# power.net
KiCad netlist of a schematic drawn in EAGLE
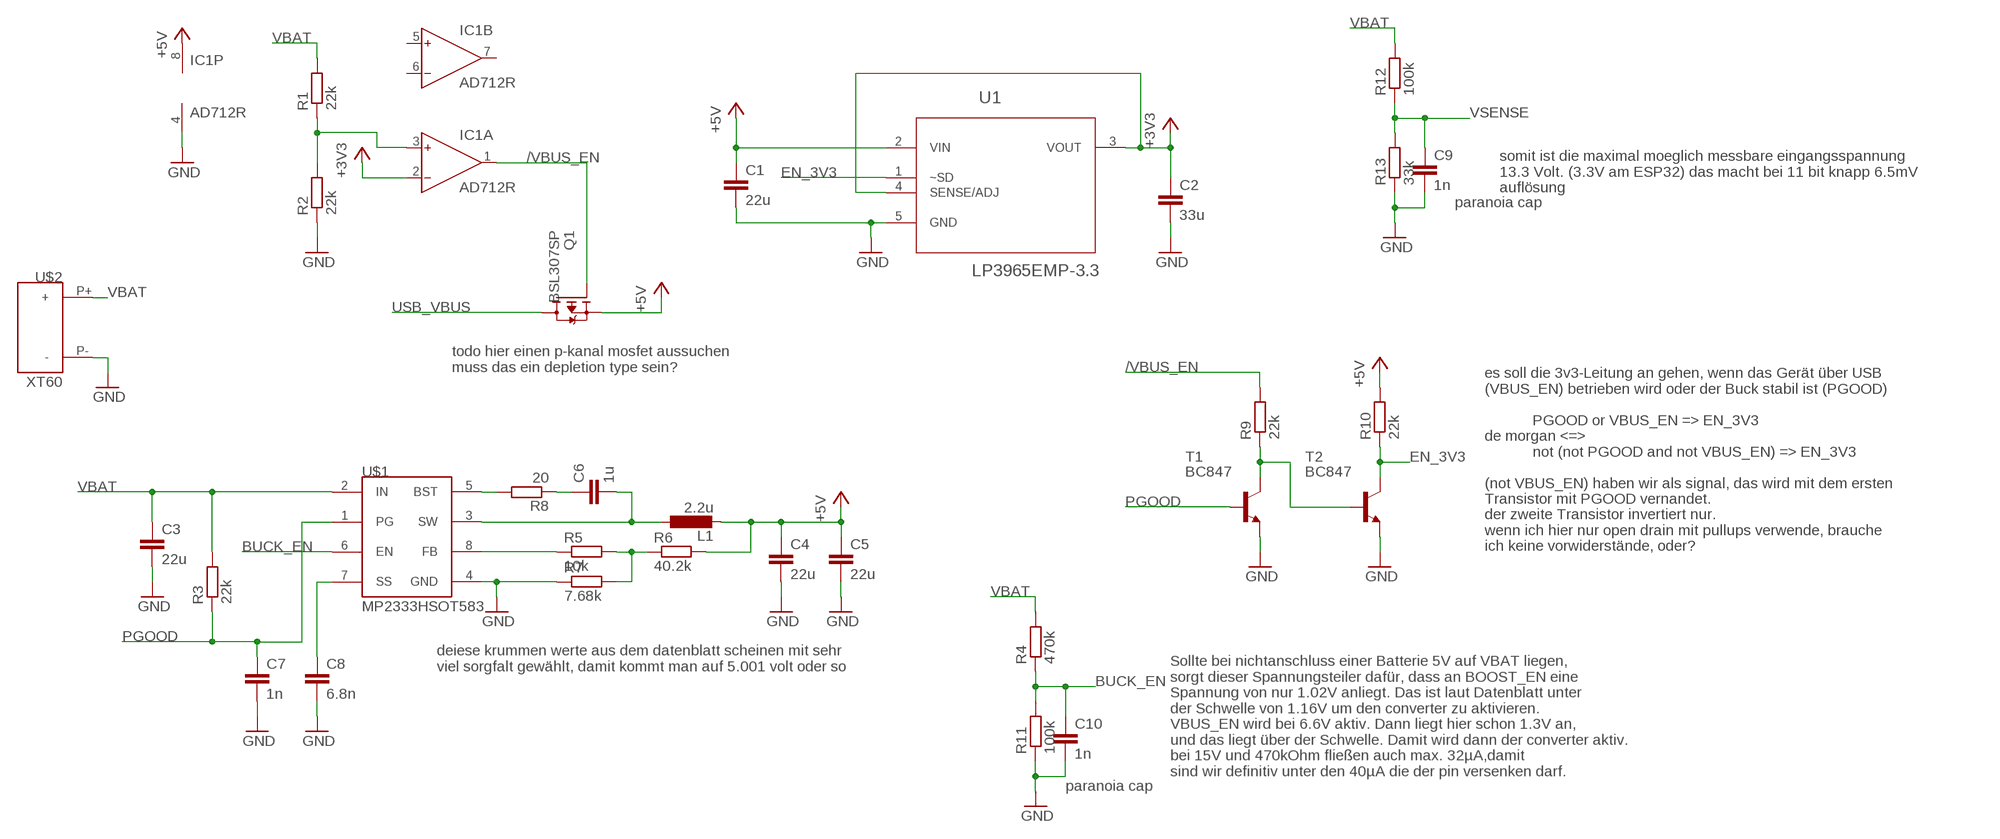
[diagram p0: schematic, sheet 1]

(export (version "E")
  (design (tool "Eeschema 10.0.6"))
  (components
    (comp (ref "C1")
      (value "22u")
      (footprint "eagle-import:C0603")
      (libsource (lib "eagle-import") (part "C-EUC0603"))
    )
    (comp (ref "C2")
      (value "33u")
      (footprint "eagle-import:C0603")
      (libsource (lib "eagle-import") (part "C-EUC0603"))
    )
    (comp (ref "C3")
      (value "22u")
      (footprint "eagle-import:C0805")
      (libsource (lib "eagle-import") (part "C-EUC0805"))
    )
    (comp (ref "C4")
      (value "22u")
      (footprint "eagle-import:C0805")
      (libsource (lib "eagle-import") (part "C-EUC0805"))
    )
    (comp (ref "C5")
      (value "22u")
      (footprint "eagle-import:C0805")
      (libsource (lib "eagle-import") (part "C-EUC0805"))
    )
    (comp (ref "C6")
      (value "1u")
      (footprint "eagle-import:C0805")
      (libsource (lib "eagle-import") (part "C-EUC0805"))
    )
    (comp (ref "C7")
      (value "1n")
      (footprint "eagle-import:C0603")
      (libsource (lib "eagle-import") (part "C-EUC0603"))
    )
    (comp (ref "C8")
      (value "6.8n")
      (footprint "eagle-import:C0603")
      (libsource (lib "eagle-import") (part "C-EUC0603"))
    )
    (comp (ref "C9")
      (value "1n")
      (footprint "eagle-import:C0603")
      (libsource (lib "eagle-import") (part "C-EUC0603"))
    )
    (comp (ref "C10")
      (value "1n")
      (footprint "eagle-import:C0603")
      (libsource (lib "eagle-import") (part "C-EUC0603"))
    )
    (comp (ref "IC1")
      (value "AD712R")
      (footprint "eagle-import:SO8")
      (fields (field (name "MF") "ALTERA CORPORATION") (field (name "MPN") "AD712KRZ"))
      (libsource (lib "eagle-import") (part "AD712R"))
    )
    (comp (ref "L1")
      (value "2.2u")
      (footprint "eagle-import:PIS2816")
      (libsource (lib "eagle-import") (part "L-EUPIS2816"))
    )
    (comp (ref "Q1")
      (value "BSL307SP")
      (footprint "eagle-import:SC74_INFINEON")
      (libsource (lib "eagle-import") (part "BSL307SP"))
    )
    (comp (ref "R1")
      (value "22k")
      (footprint "eagle-import:R0603")
      (libsource (lib "eagle-import") (part "R-EU_R0603"))
    )
    (comp (ref "R2")
      (value "22k")
      (footprint "eagle-import:R0603")
      (libsource (lib "eagle-import") (part "R-EU_R0603"))
    )
    (comp (ref "R3")
      (value "22k")
      (footprint "eagle-import:R0603")
      (libsource (lib "eagle-import") (part "R-EU_R0603"))
    )
    (comp (ref "R4")
      (value "470k")
      (footprint "eagle-import:R0603")
      (libsource (lib "eagle-import") (part "R-EU_R0603"))
    )
    (comp (ref "R5")
      (value "10k")
      (footprint "eagle-import:R0603")
      (libsource (lib "eagle-import") (part "R-EU_R0603"))
    )
    (comp (ref "R6")
      (value "40.2k")
      (footprint "eagle-import:R0603")
      (libsource (lib "eagle-import") (part "R-EU_R0603"))
    )
    (comp (ref "R7")
      (value "7.68k")
      (footprint "eagle-import:R0603")
      (libsource (lib "eagle-import") (part "R-EU_R0603"))
    )
    (comp (ref "R8")
      (value "20")
      (footprint "eagle-import:R0603")
      (libsource (lib "eagle-import") (part "R-EU_R0603"))
    )
    (comp (ref "R9")
      (value "22k")
      (footprint "eagle-import:R0603")
      (libsource (lib "eagle-import") (part "R-EU_R0603"))
    )
    (comp (ref "R10")
      (value "22k")
      (footprint "eagle-import:R0603")
      (libsource (lib "eagle-import") (part "R-EU_R0603"))
    )
    (comp (ref "R11")
      (value "100k")
      (footprint "eagle-import:R0603")
      (libsource (lib "eagle-import") (part "R-EU_R0603"))
    )
    (comp (ref "R12")
      (value "100k")
      (footprint "eagle-import:R0603")
      (libsource (lib "eagle-import") (part "R-EU_R0603"))
    )
    (comp (ref "R13")
      (value "33k")
      (footprint "eagle-import:R0603")
      (libsource (lib "eagle-import") (part "R-EU_R0603"))
    )
    (comp (ref "T1")
      (value "BC847")
      (footprint "eagle-import:SOT23")
      (libsource (lib "eagle-import") (part "BC847"))
    )
    (comp (ref "T2")
      (value "BC847")
      (footprint "eagle-import:SOT23")
      (libsource (lib "eagle-import") (part "BC847"))
    )
    (comp (ref "U$1")
      (value "MP2333HSOT583")
      (footprint "eagle-import:SOTFL50P175X60-8N")
      (libsource (lib "eagle-import") (part "MP2333HSOT583"))
    )
    (comp (ref "U$2")
      (value "XT60")
      (footprint "eagle-import:XT60-UPRIGHT")
      (libsource (lib "eagle-import") (part "XT60"))
    )
    (comp (ref "U1")
      (value "LP3965EMP-3.3")
      (footprint "eagle-import:SOT150P696X180-5N")
      (fields (field (name "MF") "Texas Instruments") (field (name "MP") "LP3965EMP-3.3/NOPB"))
      (libsource (lib "eagle-import") (part "LP3965EMP-3.3"))
    )
  )
  (nets
    (net (code "1") (name "+3V3") (class "Default")
      (node (ref "C2") (pin "1") (pinfunction "1_1") (pintype "passive"))
      (node (ref "IC1") (pin "2") (pinfunction "IN-_2") (pintype "input"))
      (node (ref "U1") (pin "3") (pinfunction "VOUT_3") (pintype "passive"))
      (node (ref "U1") (pin "4") (pinfunction "SENSE/ADJ_4") (pintype "input"))
    )
    (net (code "2") (name "+5V") (class "Default")
      (node (ref "C1") (pin "1") (pinfunction "1_1") (pintype "passive"))
      (node (ref "C4") (pin "1") (pinfunction "1_1") (pintype "passive"))
      (node (ref "C5") (pin "1") (pinfunction "1_1") (pintype "passive"))
      (node (ref "IC1") (pin "8") (pinfunction "V+_8") (pintype "power_in"))
      (node (ref "L1") (pin "2") (pinfunction "2_2") (pintype "passive"))
      (node (ref "Q1") (pin "4") (pinfunction "S_4") (pintype "passive"))
      (node (ref "R10") (pin "2") (pinfunction "2_2") (pintype "passive"))
      (node (ref "R6") (pin "2") (pinfunction "2_2") (pintype "passive"))
      (node (ref "U1") (pin "2") (pinfunction "VIN_2") (pintype "input"))
    )
    (net (code "3") (name "BUCK_EN") (class "Default")
      (node (ref "C10") (pin "1") (pinfunction "1_1") (pintype "passive"))
      (node (ref "R11") (pin "2") (pinfunction "2_2") (pintype "passive"))
      (node (ref "R4") (pin "1") (pinfunction "1_1") (pintype "passive"))
      (node (ref "U$1") (pin "6") (pinfunction "EN_6") (pintype "input"))
    )
    (net (code "4") (name "EN_3V3") (class "Default")
      (node (ref "R10") (pin "1") (pinfunction "1_1") (pintype "passive"))
      (node (ref "T2") (pin "3") (pinfunction "C_3") (pintype "passive"))
      (node (ref "U1") (pin "1") (pinfunction "~{SD}_1") (pintype "input"))
    )
    (net (code "5") (name "GND") (class "Default")
      (node (ref "C1") (pin "2") (pinfunction "2_2") (pintype "passive"))
      (node (ref "C10") (pin "2") (pinfunction "2_2") (pintype "passive"))
      (node (ref "C2") (pin "2") (pinfunction "2_2") (pintype "passive"))
      (node (ref "C3") (pin "2") (pinfunction "2_2") (pintype "passive"))
      (node (ref "C4") (pin "2") (pinfunction "2_2") (pintype "passive"))
      (node (ref "C5") (pin "2") (pinfunction "2_2") (pintype "passive"))
      (node (ref "C7") (pin "2") (pinfunction "2_2") (pintype "passive"))
      (node (ref "C8") (pin "2") (pinfunction "2_2") (pintype "passive"))
      (node (ref "C9") (pin "2") (pinfunction "2_2") (pintype "passive"))
      (node (ref "IC1") (pin "4") (pinfunction "V-_4") (pintype "power_in"))
      (node (ref "R11") (pin "1") (pinfunction "1_1") (pintype "passive"))
      (node (ref "R13") (pin "1") (pinfunction "1_1") (pintype "passive"))
      (node (ref "R2") (pin "1") (pinfunction "1_1") (pintype "passive"))
      (node (ref "R7") (pin "1") (pinfunction "1_1") (pintype "passive"))
      (node (ref "T1") (pin "2") (pinfunction "E_2") (pintype "passive"))
      (node (ref "T2") (pin "2") (pinfunction "E_2") (pintype "passive"))
      (node (ref "U$1") (pin "4") (pinfunction "GND_4") (pintype "input"))
      (node (ref "U$2") (pin "P-") (pinfunction "-_P-") (pintype "passive"))
      (node (ref "U1") (pin "5") (pinfunction "GND_5") (pintype "input"))
    )
    (net (code "6") (name "Net-(C6-Pad1)") (class "Default")
      (node (ref "C6") (pin "1") (pinfunction "1_1") (pintype "passive"))
      (node (ref "R8") (pin "1") (pinfunction "1_1") (pintype "passive"))
    )
    (net (code "7") (name "Net-(IC1A-IN+)") (class "Default")
      (node (ref "IC1") (pin "3") (pinfunction "IN+_3") (pintype "input"))
      (node (ref "R1") (pin "1") (pinfunction "1_1") (pintype "passive"))
      (node (ref "R2") (pin "2") (pinfunction "2_2") (pintype "passive"))
    )
    (net (code "8") (name "Net-(R5-Pad2)") (class "Default")
      (node (ref "R5") (pin "2") (pinfunction "2_2") (pintype "passive"))
      (node (ref "R6") (pin "1") (pinfunction "1_1") (pintype "passive"))
      (node (ref "R7") (pin "2") (pinfunction "2_2") (pintype "passive"))
    )
    (net (code "9") (name "Net-(T1-C)") (class "Default")
      (node (ref "R9") (pin "1") (pinfunction "1_1") (pintype "passive"))
      (node (ref "T1") (pin "3") (pinfunction "C_3") (pintype "passive"))
      (node (ref "T2") (pin "1") (pinfunction "B_1") (pintype "passive"))
    )
    (net (code "10") (name "Net-(U$1-BST)") (class "Default")
      (node (ref "R8") (pin "2") (pinfunction "2_2") (pintype "passive"))
      (node (ref "U$1") (pin "5") (pinfunction "BST_5") (pintype "passive"))
    )
    (net (code "11") (name "Net-(U$1-FB)") (class "Default")
      (node (ref "R5") (pin "1") (pinfunction "1_1") (pintype "passive"))
      (node (ref "U$1") (pin "8") (pinfunction "FB_8") (pintype "input"))
    )
    (net (code "12") (name "Net-(U$1-SS)") (class "Default")
      (node (ref "C8") (pin "1") (pinfunction "1_1") (pintype "passive"))
      (node (ref "U$1") (pin "7") (pinfunction "SS_7") (pintype "input"))
    )
    (net (code "13") (name "Net-(U$1-SW)") (class "Default")
      (node (ref "C6") (pin "2") (pinfunction "2_2") (pintype "passive"))
      (node (ref "L1") (pin "1") (pinfunction "1_1") (pintype "passive"))
      (node (ref "U$1") (pin "3") (pinfunction "SW_3") (pintype "passive"))
    )
    (net (code "14") (name "PGOOD") (class "Default")
      (node (ref "C7") (pin "1") (pinfunction "1_1") (pintype "passive"))
      (node (ref "R3") (pin "1") (pinfunction "1_1") (pintype "passive"))
      (node (ref "T1") (pin "1") (pinfunction "B_1") (pintype "passive"))
      (node (ref "U$1") (pin "1") (pinfunction "PG_1") (pintype "output"))
    )
    (net (code "15") (name "USB_VBUS") (class "Default")
      (node (ref "Q1") (pin "1") (pinfunction "D_1") (pintype "passive"))
      (node (ref "Q1") (pin "2") (pinfunction "D_2") (pintype "passive"))
      (node (ref "Q1") (pin "5") (pinfunction "D_5") (pintype "passive"))
      (node (ref "Q1") (pin "6") (pinfunction "D_6") (pintype "passive"))
    )
    (net (code "16") (name "VBAT") (class "Default")
      (node (ref "C3") (pin "1") (pinfunction "1_1") (pintype "passive"))
      (node (ref "R1") (pin "2") (pinfunction "2_2") (pintype "passive"))
      (node (ref "R12") (pin "2") (pinfunction "2_2") (pintype "passive"))
      (node (ref "R3") (pin "2") (pinfunction "2_2") (pintype "passive"))
      (node (ref "R4") (pin "2") (pinfunction "2_2") (pintype "passive"))
      (node (ref "U$1") (pin "2") (pinfunction "IN_2") (pintype "input"))
      (node (ref "U$2") (pin "P+") (pinfunction "+_P+") (pintype "passive"))
    )
    (net (code "17") (name "VSENSE") (class "Default")
      (node (ref "C9") (pin "1") (pinfunction "1_1") (pintype "passive"))
      (node (ref "R12") (pin "1") (pinfunction "1_1") (pintype "passive"))
      (node (ref "R13") (pin "2") (pinfunction "2_2") (pintype "passive"))
    )
    (net (code "18") (name "unconnected-(IC1B-IN+-Pad5)") (class "Default")
      (node (ref "IC1") (pin "5") (pinfunction "IN+_5") (pintype "input"))
    )
    (net (code "19") (name "unconnected-(IC1B-IN--Pad6)") (class "Default")
      (node (ref "IC1") (pin "6") (pinfunction "IN-_6") (pintype "input"))
    )
    (net (code "20") (name "unconnected-(IC1B-OUT-Pad7)") (class "Default")
      (node (ref "IC1") (pin "7") (pinfunction "OUT_7") (pintype "output"))
    )
    (net (code "21") (name "{slash}VBUS_EN") (class "Default")
      (node (ref "IC1") (pin "1") (pinfunction "OUT_1") (pintype "output"))
      (node (ref "Q1") (pin "3") (pinfunction "G_3") (pintype "passive"))
      (node (ref "R9") (pin "2") (pinfunction "2_2") (pintype "passive"))
    )
  )
)
